# WDT.net
KiCad netlist of a schematic drawn in EAGLE
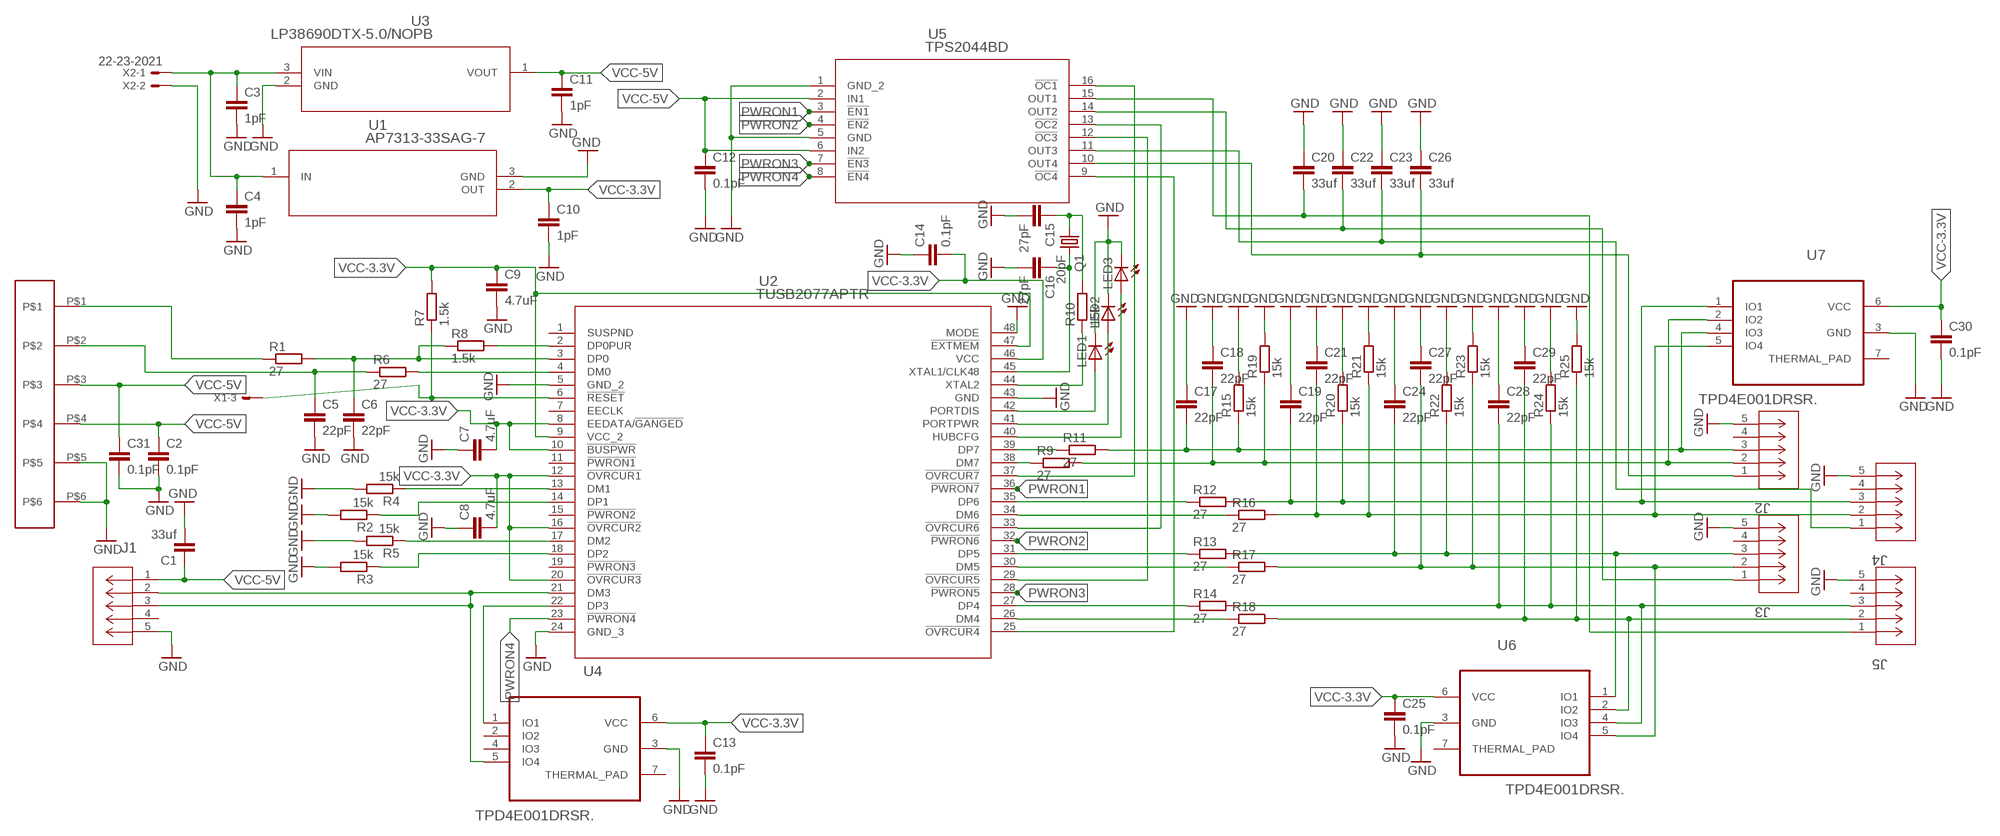
[diagram p0: schematic, sheet 1]

(export (version "E")
  (design (tool "Eeschema 10.0.6"))
  (components
    (comp (ref "C1")
      (value "33uf")
      (footprint "eagle-import:C0805")
      (libsource (lib "eagle-import") (part "C"))
    )
    (comp (ref "C2")
      (value "0.1pF")
      (footprint "eagle-import:C0805")
      (libsource (lib "eagle-import") (part "C"))
    )
    (comp (ref "C3")
      (value "1pF")
      (footprint "eagle-import:C0805")
      (libsource (lib "eagle-import") (part "C"))
    )
    (comp (ref "C4")
      (value "1pF")
      (footprint "eagle-import:C0805")
      (libsource (lib "eagle-import") (part "C"))
    )
    (comp (ref "C5")
      (value "22pF")
      (footprint "eagle-import:C0805")
      (libsource (lib "eagle-import") (part "C"))
    )
    (comp (ref "C6")
      (value "22pF")
      (footprint "eagle-import:C0805")
      (libsource (lib "eagle-import") (part "C"))
    )
    (comp (ref "C7")
      (value "4.7uF")
      (footprint "eagle-import:C0805")
      (libsource (lib "eagle-import") (part "C"))
    )
    (comp (ref "C8")
      (value "4.7uF")
      (footprint "eagle-import:C0805")
      (libsource (lib "eagle-import") (part "C"))
    )
    (comp (ref "C9")
      (value "4.7uF")
      (footprint "eagle-import:C0805")
      (libsource (lib "eagle-import") (part "C"))
    )
    (comp (ref "C10")
      (value "1pF")
      (footprint "eagle-import:C0805")
      (libsource (lib "eagle-import") (part "C"))
    )
    (comp (ref "C11")
      (value "1pF")
      (footprint "eagle-import:C0805")
      (libsource (lib "eagle-import") (part "C"))
    )
    (comp (ref "C12")
      (value "0.1pF")
      (footprint "eagle-import:C0805")
      (libsource (lib "eagle-import") (part "C"))
    )
    (comp (ref "C13")
      (value "0.1pF")
      (footprint "eagle-import:C0805")
      (libsource (lib "eagle-import") (part "C"))
    )
    (comp (ref "C14")
      (value "0.1pF")
      (footprint "eagle-import:C0805")
      (libsource (lib "eagle-import") (part "C"))
    )
    (comp (ref "C15")
      (value "27pF")
      (footprint "eagle-import:C0805")
      (libsource (lib "eagle-import") (part "C"))
    )
    (comp (ref "C16")
      (value "27pF")
      (footprint "eagle-import:C0805")
      (libsource (lib "eagle-import") (part "C"))
    )
    (comp (ref "C17")
      (value "22pF")
      (footprint "eagle-import:C0805")
      (libsource (lib "eagle-import") (part "C"))
    )
    (comp (ref "C18")
      (value "22pF")
      (footprint "eagle-import:C0805")
      (libsource (lib "eagle-import") (part "C"))
    )
    (comp (ref "C19")
      (value "22pF")
      (footprint "eagle-import:C0805")
      (libsource (lib "eagle-import") (part "C"))
    )
    (comp (ref "C20")
      (value "33uf")
      (footprint "eagle-import:C0805")
      (libsource (lib "eagle-import") (part "C"))
    )
    (comp (ref "C21")
      (value "22pF")
      (footprint "eagle-import:C0805")
      (libsource (lib "eagle-import") (part "C"))
    )
    (comp (ref "C22")
      (value "33uf")
      (footprint "eagle-import:C0805")
      (libsource (lib "eagle-import") (part "C"))
    )
    (comp (ref "C23")
      (value "33uf")
      (footprint "eagle-import:C0805")
      (libsource (lib "eagle-import") (part "C"))
    )
    (comp (ref "C24")
      (value "22pF")
      (footprint "eagle-import:C0805")
      (libsource (lib "eagle-import") (part "C"))
    )
    (comp (ref "C25")
      (value "0.1pF")
      (footprint "eagle-import:C0805")
      (libsource (lib "eagle-import") (part "C"))
    )
    (comp (ref "C26")
      (value "33uf")
      (footprint "eagle-import:C0805")
      (libsource (lib "eagle-import") (part "C"))
    )
    (comp (ref "C27")
      (value "22pF")
      (footprint "eagle-import:C0805")
      (libsource (lib "eagle-import") (part "C"))
    )
    (comp (ref "C28")
      (value "22pF")
      (footprint "eagle-import:C0805")
      (libsource (lib "eagle-import") (part "C"))
    )
    (comp (ref "C29")
      (value "22pF")
      (footprint "eagle-import:C0805")
      (libsource (lib "eagle-import") (part "C"))
    )
    (comp (ref "C30")
      (value "0.1pF")
      (footprint "eagle-import:C0805")
      (libsource (lib "eagle-import") (part "C"))
    )
    (comp (ref "C31")
      (value "0.1pF")
      (footprint "eagle-import:C0805")
      (libsource (lib "eagle-import") (part "C"))
    )
    (comp (ref "J1")
      (value "1981568-1")
      (footprint "eagle-import:CONN_1981568-1")
      (fields (field (name "MANUFACTURER_PART_NUMBER") "19815681"))
      (libsource (lib "eagle-import") (part "1981568-1"))
    )
    (comp (ref "J2")
      (value "1981568-1")
      (footprint "eagle-import:CONN_1981568-1")
      (fields (field (name "MANUFACTURER_PART_NUMBER") "19815681"))
      (libsource (lib "eagle-import") (part "1981568-1"))
    )
    (comp (ref "J3")
      (value "1981568-1")
      (footprint "eagle-import:CONN_1981568-1")
      (fields (field (name "MANUFACTURER_PART_NUMBER") "19815681"))
      (libsource (lib "eagle-import") (part "1981568-1"))
    )
    (comp (ref "J4")
      (value "1981568-1")
      (footprint "eagle-import:CONN_1981568-1")
      (fields (field (name "MANUFACTURER_PART_NUMBER") "19815681"))
      (libsource (lib "eagle-import") (part "1981568-1"))
    )
    (comp (ref "J5")
      (value "1981568-1")
      (footprint "eagle-import:CONN_1981568-1")
      (fields (field (name "MANUFACTURER_PART_NUMBER") "19815681"))
      (libsource (lib "eagle-import") (part "1981568-1"))
    )
    (comp (ref "LED1")
      (value "LED_E")
      (footprint "eagle-import:LED_1206")
      (libsource (lib "eagle-import") (part "LED_E"))
    )
    (comp (ref "LED2")
      (value "LED_E")
      (footprint "eagle-import:LED_1206")
      (libsource (lib "eagle-import") (part "LED_E"))
    )
    (comp (ref "LED3")
      (value "LED_E")
      (footprint "eagle-import:LED_1206")
      (libsource (lib "eagle-import") (part "LED_E"))
    )
    (comp (ref "Q1")
      (value "20pF")
      (footprint "eagle-import:CTS406")
      (libsource (lib "eagle-import") (part "CRYSTALCTS406"))
    )
    (comp (ref "R1")
      (value "27")
      (footprint "eagle-import:R0805")
      (libsource (lib "eagle-import") (part "R"))
    )
    (comp (ref "R2")
      (value "15k")
      (footprint "eagle-import:R0805")
      (libsource (lib "eagle-import") (part "R"))
    )
    (comp (ref "R3")
      (value "15k")
      (footprint "eagle-import:R0805")
      (libsource (lib "eagle-import") (part "R"))
    )
    (comp (ref "R4")
      (value "15k")
      (footprint "eagle-import:R0805")
      (libsource (lib "eagle-import") (part "R"))
    )
    (comp (ref "R5")
      (value "15k")
      (footprint "eagle-import:R0805")
      (libsource (lib "eagle-import") (part "R"))
    )
    (comp (ref "R6")
      (value "27")
      (footprint "eagle-import:R0805")
      (libsource (lib "eagle-import") (part "R"))
    )
    (comp (ref "R7")
      (value "1.5k")
      (footprint "eagle-import:R0805")
      (libsource (lib "eagle-import") (part "R"))
    )
    (comp (ref "R8")
      (value "1.5k")
      (footprint "eagle-import:R0805")
      (libsource (lib "eagle-import") (part "R"))
    )
    (comp (ref "R9")
      (value "27")
      (footprint "eagle-import:R0805")
      (libsource (lib "eagle-import") (part "R"))
    )
    (comp (ref "R10")
      (value "15k")
      (footprint "eagle-import:R0805")
      (libsource (lib "eagle-import") (part "R"))
    )
    (comp (ref "R11")
      (value "27")
      (footprint "eagle-import:R0805")
      (libsource (lib "eagle-import") (part "R"))
    )
    (comp (ref "R12")
      (value "27")
      (footprint "eagle-import:R0805")
      (libsource (lib "eagle-import") (part "R"))
    )
    (comp (ref "R13")
      (value "27")
      (footprint "eagle-import:R0805")
      (libsource (lib "eagle-import") (part "R"))
    )
    (comp (ref "R14")
      (value "27")
      (footprint "eagle-import:R0805")
      (libsource (lib "eagle-import") (part "R"))
    )
    (comp (ref "R15")
      (value "15k")
      (footprint "eagle-import:R0805")
      (libsource (lib "eagle-import") (part "R"))
    )
    (comp (ref "R16")
      (value "27")
      (footprint "eagle-import:R0805")
      (libsource (lib "eagle-import") (part "R"))
    )
    (comp (ref "R17")
      (value "27")
      (footprint "eagle-import:R0805")
      (libsource (lib "eagle-import") (part "R"))
    )
    (comp (ref "R18")
      (value "27")
      (footprint "eagle-import:R0805")
      (libsource (lib "eagle-import") (part "R"))
    )
    (comp (ref "R19")
      (value "15k")
      (footprint "eagle-import:R0805")
      (libsource (lib "eagle-import") (part "R"))
    )
    (comp (ref "R20")
      (value "15k")
      (footprint "eagle-import:R0805")
      (libsource (lib "eagle-import") (part "R"))
    )
    (comp (ref "R21")
      (value "15k")
      (footprint "eagle-import:R0805")
      (libsource (lib "eagle-import") (part "R"))
    )
    (comp (ref "R22")
      (value "15k")
      (footprint "eagle-import:R0805")
      (libsource (lib "eagle-import") (part "R"))
    )
    (comp (ref "R23")
      (value "15k")
      (footprint "eagle-import:R0805")
      (libsource (lib "eagle-import") (part "R"))
    )
    (comp (ref "R24")
      (value "15k")
      (footprint "eagle-import:R0805")
      (libsource (lib "eagle-import") (part "R"))
    )
    (comp (ref "R25")
      (value "15k")
      (footprint "eagle-import:R0805")
      (libsource (lib "eagle-import") (part "R"))
    )
    (comp (ref "U$1")
      (value "HEADER-6PIN-50MIL")
      (footprint "eagle-import:PIN-4-1.27MMPITCH")
      (libsource (lib "eagle-import") (part "HEADER-6PIN-50MIL"))
    )
    (comp (ref "U1")
      (value "AP7313-33SAG-7")
      (footprint "eagle-import:SOT-23")
      (fields (field (name "MANUFACTURER_PART_NUMBER") "AP731333SAG7"))
      (libsource (lib "eagle-import") (part "AP7313-33SAG-7"))
    )
    (comp (ref "U2")
      (value "TUSB2077APTR")
      (footprint "eagle-import:PT48")
      (libsource (lib "eagle-import") (part "TUSB2077APTR"))
    )
    (comp (ref "U3")
      (value "LP38690DTX-5.0/NOPB")
      (footprint "eagle-import:TD03B")
      (fields (field (name "MANUFACTURER_PART_NUMBER") "LP38690DTX5.0NOPB"))
      (libsource (lib "eagle-import") (part "LP38690DTX-5.0/NOPB"))
    )
    (comp (ref "U4")
      (value "TPD4E001DRSR.")
      (footprint "eagle-import:SON95P315X315X80-7N")
      (fields (field (name "MF") "Texas Instruments") (field (name "MP") "TPD4E001DRSR"))
      (libsource (lib "eagle-import") (part "TPD4E001DRSR."))
    )
    (comp (ref "U5")
      (value "TPS2044BD")
      (footprint "eagle-import:D16")
      (libsource (lib "eagle-import") (part "TPS2044BD"))
    )
    (comp (ref "U6")
      (value "TPD4E001DRSR.")
      (footprint "eagle-import:SON95P315X315X80-7N")
      (fields (field (name "MF") "Texas Instruments") (field (name "MP") "TPD4E001DRSR"))
      (libsource (lib "eagle-import") (part "TPD4E001DRSR."))
    )
    (comp (ref "U7")
      (value "TPD4E001DRSR.")
      (footprint "eagle-import:SON95P315X315X80-7N")
      (fields (field (name "MF") "Texas Instruments") (field (name "MP") "TPD4E001DRSR"))
      (libsource (lib "eagle-import") (part "TPD4E001DRSR."))
    )
    (comp (ref "X1")
      (value "22-23-2051")
      (footprint "eagle-import:22-23-2051")
      (fields (field (name "MF") "MOLEX"))
      (libsource (lib "eagle-import") (part "22-23-2051"))
    )
    (comp (ref "X2")
      (value "22-23-2021")
      (footprint "eagle-import:22-23-2021")
      (fields (field (name "MF") "MOLEX"))
      (libsource (lib "eagle-import") (part "22-23-2021"))
    )
  )
  (nets
    (net (code "1") (name "GND") (class "Default")
      (node (ref "C1") (pin "2") (pinfunction "2_2") (pintype "passive"))
      (node (ref "C10") (pin "2") (pinfunction "2_2") (pintype "passive"))
      (node (ref "C11") (pin "2") (pinfunction "2_2") (pintype "passive"))
      (node (ref "C12") (pin "2") (pinfunction "2_2") (pintype "passive"))
      (node (ref "C13") (pin "2") (pinfunction "2_2") (pintype "passive"))
      (node (ref "C14") (pin "1") (pinfunction "1_1") (pintype "passive"))
      (node (ref "C15") (pin "2") (pinfunction "2_2") (pintype "passive"))
      (node (ref "C16") (pin "2") (pinfunction "2_2") (pintype "passive"))
      (node (ref "C17") (pin "1") (pinfunction "1_1") (pintype "passive"))
      (node (ref "C18") (pin "1") (pinfunction "1_1") (pintype "passive"))
      (node (ref "C19") (pin "1") (pinfunction "1_1") (pintype "passive"))
      (node (ref "C2") (pin "2") (pinfunction "2_2") (pintype "passive"))
      (node (ref "C20") (pin "1") (pinfunction "1_1") (pintype "passive"))
      (node (ref "C21") (pin "1") (pinfunction "1_1") (pintype "passive"))
      (node (ref "C22") (pin "1") (pinfunction "1_1") (pintype "passive"))
      (node (ref "C23") (pin "1") (pinfunction "1_1") (pintype "passive"))
      (node (ref "C24") (pin "1") (pinfunction "1_1") (pintype "passive"))
      (node (ref "C25") (pin "2") (pinfunction "2_2") (pintype "passive"))
      (node (ref "C26") (pin "1") (pinfunction "1_1") (pintype "passive"))
      (node (ref "C27") (pin "1") (pinfunction "1_1") (pintype "passive"))
      (node (ref "C28") (pin "1") (pinfunction "1_1") (pintype "passive"))
      (node (ref "C29") (pin "1") (pinfunction "1_1") (pintype "passive"))
      (node (ref "C3") (pin "2") (pinfunction "2_2") (pintype "passive"))
      (node (ref "C30") (pin "2") (pinfunction "2_2") (pintype "passive"))
      (node (ref "C31") (pin "2") (pinfunction "2_2") (pintype "passive"))
      (node (ref "C4") (pin "2") (pinfunction "2_2") (pintype "passive"))
      (node (ref "C5") (pin "2") (pinfunction "2_2") (pintype "passive"))
      (node (ref "C6") (pin "2") (pinfunction "2_2") (pintype "passive"))
      (node (ref "C7") (pin "1") (pinfunction "1_1") (pintype "passive"))
      (node (ref "C8") (pin "1") (pinfunction "1_1") (pintype "passive"))
      (node (ref "C9") (pin "2") (pinfunction "2_2") (pintype "passive"))
      (node (ref "J1") (pin "5") (pinfunction "5_5") (pintype "passive"))
      (node (ref "J2") (pin "5") (pinfunction "5_5") (pintype "passive"))
      (node (ref "J3") (pin "5") (pinfunction "5_5") (pintype "passive"))
      (node (ref "J4") (pin "5") (pinfunction "5_5") (pintype "passive"))
      (node (ref "J5") (pin "5") (pinfunction "5_5") (pintype "passive"))
      (node (ref "LED1") (pin "C") (pinfunction "C_C") (pintype "passive"))
      (node (ref "LED2") (pin "C") (pinfunction "C_C") (pintype "passive"))
      (node (ref "LED3") (pin "C") (pinfunction "C_C") (pintype "passive"))
      (node (ref "R15") (pin "2") (pinfunction "2_2") (pintype "passive"))
      (node (ref "R19") (pin "2") (pinfunction "2_2") (pintype "passive"))
      (node (ref "R2") (pin "2") (pinfunction "2_2") (pintype "passive"))
      (node (ref "R20") (pin "2") (pinfunction "2_2") (pintype "passive"))
      (node (ref "R21") (pin "2") (pinfunction "2_2") (pintype "passive"))
      (node (ref "R22") (pin "2") (pinfunction "2_2") (pintype "passive"))
      (node (ref "R23") (pin "2") (pinfunction "2_2") (pintype "passive"))
      (node (ref "R24") (pin "2") (pinfunction "2_2") (pintype "passive"))
      (node (ref "R25") (pin "2") (pinfunction "2_2") (pintype "passive"))
      (node (ref "R3") (pin "2") (pinfunction "2_2") (pintype "passive"))
      (node (ref "R4") (pin "2") (pinfunction "2_2") (pintype "passive"))
      (node (ref "R5") (pin "2") (pinfunction "2_2") (pintype "passive"))
      (node (ref "U$1") (pin "P$5") (pinfunction "P$5_P$5") (pintype "bidirectional"))
      (node (ref "U$1") (pin "P$6") (pinfunction "P$6_P$6") (pintype "bidirectional"))
      (node (ref "U1") (pin "3") (pinfunction "GND_3") (pintype "power_in"))
      (node (ref "U2") (pin "24") (pinfunction "GND_3_24") (pintype "power_in"))
      (node (ref "U2") (pin "43") (pinfunction "GND_43") (pintype "power_in"))
      (node (ref "U2") (pin "48") (pinfunction "MODE_48") (pintype "input"))
      (node (ref "U2") (pin "5") (pinfunction "GND_2_5") (pintype "power_in"))
      (node (ref "U3") (pin "2") (pinfunction "GND_2") (pintype "passive"))
      (node (ref "U4") (pin "3") (pinfunction "GND_3") (pintype "passive"))
      (node (ref "U5") (pin "1") (pinfunction "GND_2_1") (pintype "power_in"))
      (node (ref "U5") (pin "5") (pinfunction "GND_5") (pintype "power_in"))
      (node (ref "U6") (pin "3") (pinfunction "GND_3") (pintype "passive"))
      (node (ref "U7") (pin "3") (pinfunction "GND_3") (pintype "passive"))
      (node (ref "X2") (pin "2") (pinfunction "S_2") (pintype "passive"))
    )
    (net (code "2") (name "Net-(C5-Pad1)") (class "Default")
      (node (ref "C5") (pin "1") (pinfunction "1_1") (pintype "passive"))
      (node (ref "R6") (pin "1") (pinfunction "1_1") (pintype "passive"))
      (node (ref "U$1") (pin "P$2") (pinfunction "P$2_P$2") (pintype "bidirectional"))
    )
    (net (code "3") (name "Net-(C15-Pad1)") (class "Default")
      (node (ref "C15") (pin "1") (pinfunction "1_1") (pintype "passive"))
      (node (ref "Q1") (pin "1") (pinfunction "1_1") (pintype "passive"))
      (node (ref "R10") (pin "2") (pinfunction "2_2") (pintype "passive"))
    )
    (net (code "4") (name "Net-(Q1-2)") (class "Default")
      (node (ref "C16") (pin "1") (pinfunction "1_1") (pintype "passive"))
      (node (ref "Q1") (pin "3") (pinfunction "2_3") (pintype "passive"))
      (node (ref "U2") (pin "45") (pinfunction "XTAL1/CLK48_45") (pintype "input"))
    )
    (net (code "5") (name "Net-(R1-Pad1)") (class "Default")
      (node (ref "R1") (pin "1") (pinfunction "1_1") (pintype "passive"))
      (node (ref "U$1") (pin "P$1") (pinfunction "P$1_P$1") (pintype "bidirectional"))
    )
    (net (code "6") (name "Net-(U1-IN)") (class "Default")
      (node (ref "C3") (pin "1") (pinfunction "1_1") (pintype "passive"))
      (node (ref "C4") (pin "1") (pinfunction "1_1") (pintype "passive"))
      (node (ref "U1") (pin "1") (pinfunction "IN_1") (pintype "input"))
      (node (ref "U3") (pin "3") (pinfunction "VIN_3") (pintype "input"))
      (node (ref "X2") (pin "1") (pinfunction "S_1") (pintype "passive"))
    )
    (net (code "7") (name "Net-(U2-DM0)") (class "Default")
      (node (ref "R6") (pin "2") (pinfunction "2_2") (pintype "passive"))
      (node (ref "U2") (pin "4") (pinfunction "DM0_4") (pintype "bidirectional"))
    )
    (net (code "8") (name "Net-(U2-DM1)") (class "Default")
      (node (ref "R4") (pin "1") (pinfunction "1_1") (pintype "passive"))
      (node (ref "U2") (pin "13") (pinfunction "DM1_13") (pintype "bidirectional"))
    )
    (net (code "9") (name "Net-(U2-DM2)") (class "Default")
      (node (ref "R5") (pin "1") (pinfunction "1_1") (pintype "passive"))
      (node (ref "U2") (pin "17") (pinfunction "DM2_17") (pintype "bidirectional"))
    )
    (net (code "10") (name "Net-(U2-DM3)") (class "Default")
      (node (ref "J1") (pin "2") (pinfunction "2_2") (pintype "passive"))
      (node (ref "J1") (pin "3") (pinfunction "3_3") (pintype "passive"))
      (node (ref "U2") (pin "21") (pinfunction "DM3_21") (pintype "bidirectional"))
      (node (ref "U4") (pin "5") (pinfunction "IO4_5") (pintype "output"))
    )
    (net (code "11") (name "Net-(U2-DM4)") (class "Default")
      (node (ref "R18") (pin "1") (pinfunction "1_1") (pintype "passive"))
      (node (ref "U2") (pin "26") (pinfunction "DM4_26") (pintype "bidirectional"))
    )
    (net (code "12") (name "Net-(U2-DM5)") (class "Default")
      (node (ref "R17") (pin "1") (pinfunction "1_1") (pintype "passive"))
      (node (ref "U2") (pin "30") (pinfunction "DM5_30") (pintype "bidirectional"))
    )
    (net (code "13") (name "Net-(U2-DM6)") (class "Default")
      (node (ref "R16") (pin "1") (pinfunction "1_1") (pintype "passive"))
      (node (ref "U2") (pin "34") (pinfunction "DM6_34") (pintype "bidirectional"))
    )
    (net (code "14") (name "Net-(U2-DM7)") (class "Default")
      (node (ref "R9") (pin "1") (pinfunction "1_1") (pintype "passive"))
      (node (ref "U2") (pin "38") (pinfunction "DM7_38") (pintype "bidirectional"))
    )
    (net (code "15") (name "Net-(U2-DP0)") (class "Default")
      (node (ref "C6") (pin "1") (pinfunction "1_1") (pintype "passive"))
      (node (ref "R1") (pin "2") (pinfunction "2_2") (pintype "passive"))
      (node (ref "R8") (pin "1") (pinfunction "1_1") (pintype "passive"))
      (node (ref "U2") (pin "3") (pinfunction "DP0_3") (pintype "passive"))
    )
    (net (code "16") (name "Net-(U2-DP0PUR)") (class "Default")
      (node (ref "R8") (pin "2") (pinfunction "2_2") (pintype "passive"))
      (node (ref "U2") (pin "2") (pinfunction "DP0PUR_2") (pintype "output"))
    )
    (net (code "17") (name "Net-(U2-DP1)") (class "Default")
      (node (ref "R2") (pin "1") (pinfunction "1_1") (pintype "passive"))
      (node (ref "U2") (pin "14") (pinfunction "DP1_14") (pintype "bidirectional"))
    )
    (net (code "18") (name "Net-(U2-DP2)") (class "Default")
      (node (ref "R3") (pin "1") (pinfunction "1_1") (pintype "passive"))
      (node (ref "U2") (pin "18") (pinfunction "DP2_18") (pintype "bidirectional"))
    )
    (net (code "19") (name "Net-(U2-DP3)") (class "Default")
      (node (ref "U2") (pin "22") (pinfunction "DP3_22") (pintype "bidirectional"))
      (node (ref "U4") (pin "1") (pinfunction "IO1_1") (pintype "output"))
    )
    (net (code "20") (name "Net-(U2-DP4)") (class "Default")
      (node (ref "R14") (pin "1") (pinfunction "1_1") (pintype "passive"))
      (node (ref "U2") (pin "27") (pinfunction "DP4_27") (pintype "bidirectional"))
    )
    (net (code "21") (name "Net-(U2-DP5)") (class "Default")
      (node (ref "R13") (pin "1") (pinfunction "1_1") (pintype "passive"))
      (node (ref "U2") (pin "31") (pinfunction "DP5_31") (pintype "bidirectional"))
    )
    (net (code "22") (name "Net-(U2-DP6)") (class "Default")
      (node (ref "R12") (pin "1") (pinfunction "1_1") (pintype "passive"))
      (node (ref "U2") (pin "35") (pinfunction "DP6_35") (pintype "bidirectional"))
    )
    (net (code "23") (name "Net-(U2-DP7)") (class "Default")
      (node (ref "R11") (pin "1") (pinfunction "1_1") (pintype "passive"))
      (node (ref "U2") (pin "39") (pinfunction "DP7_39") (pintype "bidirectional"))
    )
    (net (code "24") (name "Net-(U2-HUBCFG)") (class "Default")
      (node (ref "LED3") (pin "A") (pinfunction "A_A") (pintype "passive"))
      (node (ref "U2") (pin "40") (pinfunction "HUBCFG_40") (pintype "output"))
    )
    (net (code "25") (name "Net-(U2-PORTDIS)") (class "Default")
      (node (ref "LED1") (pin "A") (pinfunction "A_A") (pintype "passive"))
      (node (ref "U2") (pin "42") (pinfunction "PORTDIS_42") (pintype "output"))
    )
    (net (code "26") (name "Net-(U2-PORTPWR)") (class "Default")
      (node (ref "LED2") (pin "A") (pinfunction "A_A") (pintype "passive"))
      (node (ref "U2") (pin "41") (pinfunction "PORTPWR_41") (pintype "output"))
    )
    (net (code "27") (name "Net-(U2-XTAL2)") (class "Default")
      (node (ref "R10") (pin "1") (pinfunction "1_1") (pintype "passive"))
      (node (ref "U2") (pin "44") (pinfunction "XTAL2_44") (pintype "output"))
    )
    (net (code "28") (name "Net-(U2-~{OVRCUR4})") (class "Default")
      (node (ref "U2") (pin "25") (pinfunction "~{OVRCUR4}_25") (pintype "input"))
      (node (ref "U5") (pin "9") (pinfunction "~{OC4}_9") (pintype "output"))
    )
    (net (code "29") (name "Net-(U2-~{OVRCUR5})") (class "Default")
      (node (ref "U2") (pin "29") (pinfunction "~{OVRCUR5}_29") (pintype "input"))
      (node (ref "U5") (pin "12") (pinfunction "~{OC3}_12") (pintype "output"))
    )
    (net (code "30") (name "Net-(U2-~{OVRCUR6})") (class "Default")
      (node (ref "U2") (pin "33") (pinfunction "~{OVRCUR6}_33") (pintype "input"))
      (node (ref "U5") (pin "13") (pinfunction "~{OC2}_13") (pintype "output"))
    )
    (net (code "31") (name "Net-(U2-~{OVRCUR7})") (class "Default")
      (node (ref "U2") (pin "37") (pinfunction "~{OVRCUR7}_37") (pintype "input"))
      (node (ref "U5") (pin "16") (pinfunction "~{OC1}_16") (pintype "output"))
    )
    (net (code "32") (name "Net-(U2-~{RESET})") (class "Default")
      (node (ref "R7") (pin "1") (pinfunction "1_1") (pintype "passive"))
      (node (ref "U2") (pin "6") (pinfunction "~{RESET}_6") (pintype "input"))
      (node (ref "X1") (pin "3") (pinfunction "S_3") (pintype "passive"))
    )
    (net (code "33") (name "Net-(U5-OUT1)") (class "Default")
      (node (ref "C20") (pin "2") (pinfunction "2_2") (pintype "passive"))
      (node (ref "J5") (pin "1") (pinfunction "1_1") (pintype "passive"))
      (node (ref "U5") (pin "15") (pinfunction "OUT1_15") (pintype "output"))
    )
    (net (code "34") (name "Net-(U5-OUT2)") (class "Default")
      (node (ref "C22") (pin "2") (pinfunction "2_2") (pintype "passive"))
      (node (ref "J3") (pin "1") (pinfunction "1_1") (pintype "passive"))
      (node (ref "U5") (pin "14") (pinfunction "OUT2_14") (pintype "output"))
    )
    (net (code "35") (name "Net-(U5-OUT3)") (class "Default")
      (node (ref "C23") (pin "2") (pinfunction "2_2") (pintype "passive"))
      (node (ref "J4") (pin "1") (pinfunction "1_1") (pintype "passive"))
      (node (ref "U5") (pin "11") (pinfunction "OUT3_11") (pintype "output"))
    )
    (net (code "36") (name "Net-(U5-OUT4)") (class "Default")
      (node (ref "C26") (pin "2") (pinfunction "2_2") (pintype "passive"))
      (node (ref "J2") (pin "1") (pinfunction "1_1") (pintype "passive"))
      (node (ref "U5") (pin "10") (pinfunction "OUT4_10") (pintype "output"))
    )
    (net (code "37") (name "Net-(U6-IO1)") (class "Default")
      (node (ref "C24") (pin "2") (pinfunction "2_2") (pintype "passive"))
      (node (ref "J3") (pin "3") (pinfunction "3_3") (pintype "passive"))
      (node (ref "R13") (pin "2") (pinfunction "2_2") (pintype "passive"))
      (node (ref "R22") (pin "1") (pinfunction "1_1") (pintype "passive"))
      (node (ref "U6") (pin "1") (pinfunction "IO1_1") (pintype "output"))
    )
    (net (code "38") (name "Net-(U6-IO2)") (class "Default")
      (node (ref "C29") (pin "2") (pinfunction "2_2") (pintype "passive"))
      (node (ref "J5") (pin "2") (pinfunction "2_2") (pintype "passive"))
      (node (ref "R18") (pin "2") (pinfunction "2_2") (pintype "passive"))
      (node (ref "R25") (pin "1") (pinfunction "1_1") (pintype "passive"))
      (node (ref "U6") (pin "2") (pinfunction "IO2_2") (pintype "output"))
    )
    (net (code "39") (name "Net-(U6-IO3)") (class "Default")
      (node (ref "C28") (pin "2") (pinfunction "2_2") (pintype "passive"))
      (node (ref "J5") (pin "3") (pinfunction "3_3") (pintype "passive"))
      (node (ref "R14") (pin "2") (pinfunction "2_2") (pintype "passive"))
      (node (ref "R24") (pin "1") (pinfunction "1_1") (pintype "passive"))
      (node (ref "U6") (pin "4") (pinfunction "IO3_4") (pintype "output"))
    )
    (net (code "40") (name "Net-(U6-IO4)") (class "Default")
      (node (ref "C27") (pin "2") (pinfunction "2_2") (pintype "passive"))
      (node (ref "J3") (pin "2") (pinfunction "2_2") (pintype "passive"))
      (node (ref "R17") (pin "2") (pinfunction "2_2") (pintype "passive"))
      (node (ref "R23") (pin "1") (pinfunction "1_1") (pintype "passive"))
      (node (ref "U6") (pin "5") (pinfunction "IO4_5") (pintype "output"))
    )
    (net (code "41") (name "Net-(U7-IO1)") (class "Default")
      (node (ref "C19") (pin "2") (pinfunction "2_2") (pintype "passive"))
      (node (ref "J4") (pin "3") (pinfunction "3_3") (pintype "passive"))
      (node (ref "R12") (pin "2") (pinfunction "2_2") (pintype "passive"))
      (node (ref "R20") (pin "1") (pinfunction "1_1") (pintype "passive"))
      (node (ref "U7") (pin "1") (pinfunction "IO1_1") (pintype "output"))
    )
    (net (code "42") (name "Net-(U7-IO2)") (class "Default")
      (node (ref "C18") (pin "2") (pinfunction "2_2") (pintype "passive"))
      (node (ref "J2") (pin "2") (pinfunction "2_2") (pintype "passive"))
      (node (ref "R19") (pin "1") (pinfunction "1_1") (pintype "passive"))
      (node (ref "R9") (pin "2") (pinfunction "2_2") (pintype "passive"))
      (node (ref "U7") (pin "2") (pinfunction "IO2_2") (pintype "output"))
    )
    (net (code "43") (name "Net-(U7-IO3)") (class "Default")
      (node (ref "C17") (pin "2") (pinfunction "2_2") (pintype "passive"))
      (node (ref "J2") (pin "3") (pinfunction "3_3") (pintype "passive"))
      (node (ref "R11") (pin "2") (pinfunction "2_2") (pintype "passive"))
      (node (ref "R15") (pin "1") (pinfunction "1_1") (pintype "passive"))
      (node (ref "U7") (pin "4") (pinfunction "IO3_4") (pintype "output"))
    )
    (net (code "44") (name "Net-(U7-IO4)") (class "Default")
      (node (ref "C21") (pin "2") (pinfunction "2_2") (pintype "passive"))
      (node (ref "J4") (pin "2") (pinfunction "2_2") (pintype "passive"))
      (node (ref "R16") (pin "2") (pinfunction "2_2") (pintype "passive"))
      (node (ref "R21") (pin "1") (pinfunction "1_1") (pintype "passive"))
      (node (ref "U7") (pin "5") (pinfunction "IO4_5") (pintype "output"))
    )
    (net (code "45") (name "PWRON1") (class "Default")
      (node (ref "U2") (pin "36") (pinfunction "~{PWRON7}_36") (pintype "output"))
      (node (ref "U5") (pin "3") (pinfunction "~{EN1}_3") (pintype "input"))
    )
    (net (code "46") (name "PWRON2") (class "Default")
      (node (ref "U2") (pin "32") (pinfunction "~{PWRON6}_32") (pintype "output"))
      (node (ref "U5") (pin "4") (pinfunction "~{EN2}_4") (pintype "input"))
    )
    (net (code "47") (name "PWRON3") (class "Default")
      (node (ref "U2") (pin "28") (pinfunction "~{PWRON5}_28") (pintype "output"))
      (node (ref "U5") (pin "7") (pinfunction "~{EN3}_7") (pintype "input"))
    )
    (net (code "48") (name "PWRON4") (class "Default")
      (node (ref "U2") (pin "23") (pinfunction "~{PWRON4}_23") (pintype "output"))
      (node (ref "U5") (pin "8") (pinfunction "~{EN4}_8") (pintype "input"))
    )
    (net (code "49") (name "VCC-3.3V") (class "Default")
      (node (ref "C10") (pin "1") (pinfunction "1_1") (pintype "passive"))
      (node (ref "C13") (pin "1") (pinfunction "1_1") (pintype "passive"))
      (node (ref "C14") (pin "2") (pinfunction "2_2") (pintype "passive"))
      (node (ref "C25") (pin "1") (pinfunction "1_1") (pintype "passive"))
      (node (ref "C30") (pin "1") (pinfunction "1_1") (pintype "passive"))
      (node (ref "C7") (pin "2") (pinfunction "2_2") (pintype "passive"))
      (node (ref "C8") (pin "2") (pinfunction "2_2") (pintype "passive"))
      (node (ref "C9") (pin "1") (pinfunction "1_1") (pintype "passive"))
      (node (ref "R7") (pin "2") (pinfunction "2_2") (pintype "passive"))
      (node (ref "U1") (pin "2") (pinfunction "OUT_2") (pintype "output"))
      (node (ref "U2") (pin "10") (pinfunction "~{BUSPWR}_10") (pintype "passive"))
      (node (ref "U2") (pin "12") (pinfunction "~{OVRCUR1}_12") (pintype "input"))
      (node (ref "U2") (pin "16") (pinfunction "~{OVRCUR2}_16") (pintype "input"))
      (node (ref "U2") (pin "20") (pinfunction "~{OVRCUR3}_20") (pintype "input"))
      (node (ref "U2") (pin "46") (pinfunction "VCC_46") (pintype "power_in"))
      (node (ref "U2") (pin "47") (pinfunction "~{EXTMEM}_47") (pintype "input"))
      (node (ref "U2") (pin "8") (pinfunction "EEDATA/~{GANGED}_8") (pintype "bidirectional"))
      (node (ref "U2") (pin "9") (pinfunction "VCC_2_9") (pintype "power_in"))
      (node (ref "U4") (pin "6") (pinfunction "VCC_6") (pintype "power_in"))
      (node (ref "U6") (pin "6") (pinfunction "VCC_6") (pintype "power_in"))
      (node (ref "U7") (pin "6") (pinfunction "VCC_6") (pintype "power_in"))
    )
    (net (code "50") (name "VCC-5V") (class "Default")
      (node (ref "C1") (pin "1") (pinfunction "1_1") (pintype "passive"))
      (node (ref "C11") (pin "1") (pinfunction "1_1") (pintype "passive"))
      (node (ref "C12") (pin "1") (pinfunction "1_1") (pintype "passive"))
      (node (ref "C2") (pin "1") (pinfunction "1_1") (pintype "passive"))
      (node (ref "C31") (pin "1") (pinfunction "1_1") (pintype "passive"))
      (node (ref "J1") (pin "1") (pinfunction "1_1") (pintype "passive"))
      (node (ref "U$1") (pin "P$3") (pinfunction "P$3_P$3") (pintype "bidirectional"))
      (node (ref "U$1") (pin "P$4") (pinfunction "P$4_P$4") (pintype "bidirectional"))
      (node (ref "U3") (pin "1") (pinfunction "VOUT_1") (pintype "output"))
      (node (ref "U5") (pin "2") (pinfunction "IN1_2") (pintype "input"))
      (node (ref "U5") (pin "6") (pinfunction "IN2_6") (pintype "input"))
    )
    (net (code "51") (name "unconnected-(J1-Pad4)") (class "Default")
      (node (ref "J1") (pin "4") (pinfunction "4_4") (pintype "passive"))
    )
    (net (code "52") (name "unconnected-(J2-Pad4)") (class "Default")
      (node (ref "J2") (pin "4") (pinfunction "4_4") (pintype "passive"))
    )
    (net (code "53") (name "unconnected-(J3-Pad4)") (class "Default")
      (node (ref "J3") (pin "4") (pinfunction "4_4") (pintype "passive"))
    )
    (net (code "54") (name "unconnected-(J4-Pad4)") (class "Default")
      (node (ref "J4") (pin "4") (pinfunction "4_4") (pintype "passive"))
    )
    (net (code "55") (name "unconnected-(J5-Pad4)") (class "Default")
      (node (ref "J5") (pin "4") (pinfunction "4_4") (pintype "passive"))
    )
    (net (code "56") (name "unconnected-(U2-EECLK-Pad7)") (class "Default")
      (node (ref "U2") (pin "7") (pinfunction "EECLK_7") (pintype "output"))
    )
    (net (code "57") (name "unconnected-(U2-SUSPND-Pad1)") (class "Default")
      (node (ref "U2") (pin "1") (pinfunction "SUSPND_1") (pintype "output"))
    )
    (net (code "58") (name "unconnected-(U2-~{PWRON1}-Pad11)") (class "Default")
      (node (ref "U2") (pin "11") (pinfunction "~{PWRON1}_11") (pintype "output"))
    )
    (net (code "59") (name "unconnected-(U2-~{PWRON2}-Pad15)") (class "Default")
      (node (ref "U2") (pin "15") (pinfunction "~{PWRON2}_15") (pintype "output"))
    )
    (net (code "60") (name "unconnected-(U2-~{PWRON3}-Pad19)") (class "Default")
      (node (ref "U2") (pin "19") (pinfunction "~{PWRON3}_19") (pintype "output"))
    )
    (net (code "61") (name "unconnected-(U4-IO2-Pad2)") (class "Default")
      (node (ref "U4") (pin "2") (pinfunction "IO2_2") (pintype "output"))
    )
    (net (code "62") (name "unconnected-(U4-IO3-Pad4)") (class "Default")
      (node (ref "U4") (pin "4") (pinfunction "IO3_4") (pintype "output"))
    )
    (net (code "63") (name "unconnected-(U4-THERMAL_PAD-Pad7)") (class "Default")
      (node (ref "U4") (pin "7") (pinfunction "THERMAL_PAD_7") (pintype "passive"))
    )
    (net (code "64") (name "unconnected-(U6-THERMAL_PAD-Pad7)") (class "Default")
      (node (ref "U6") (pin "7") (pinfunction "THERMAL_PAD_7") (pintype "passive"))
    )
    (net (code "65") (name "unconnected-(U7-THERMAL_PAD-Pad7)") (class "Default")
      (node (ref "U7") (pin "7") (pinfunction "THERMAL_PAD_7") (pintype "passive"))
    )
  )
)
